# commu.net
KiCad netlist of a schematic drawn in Altium Designer
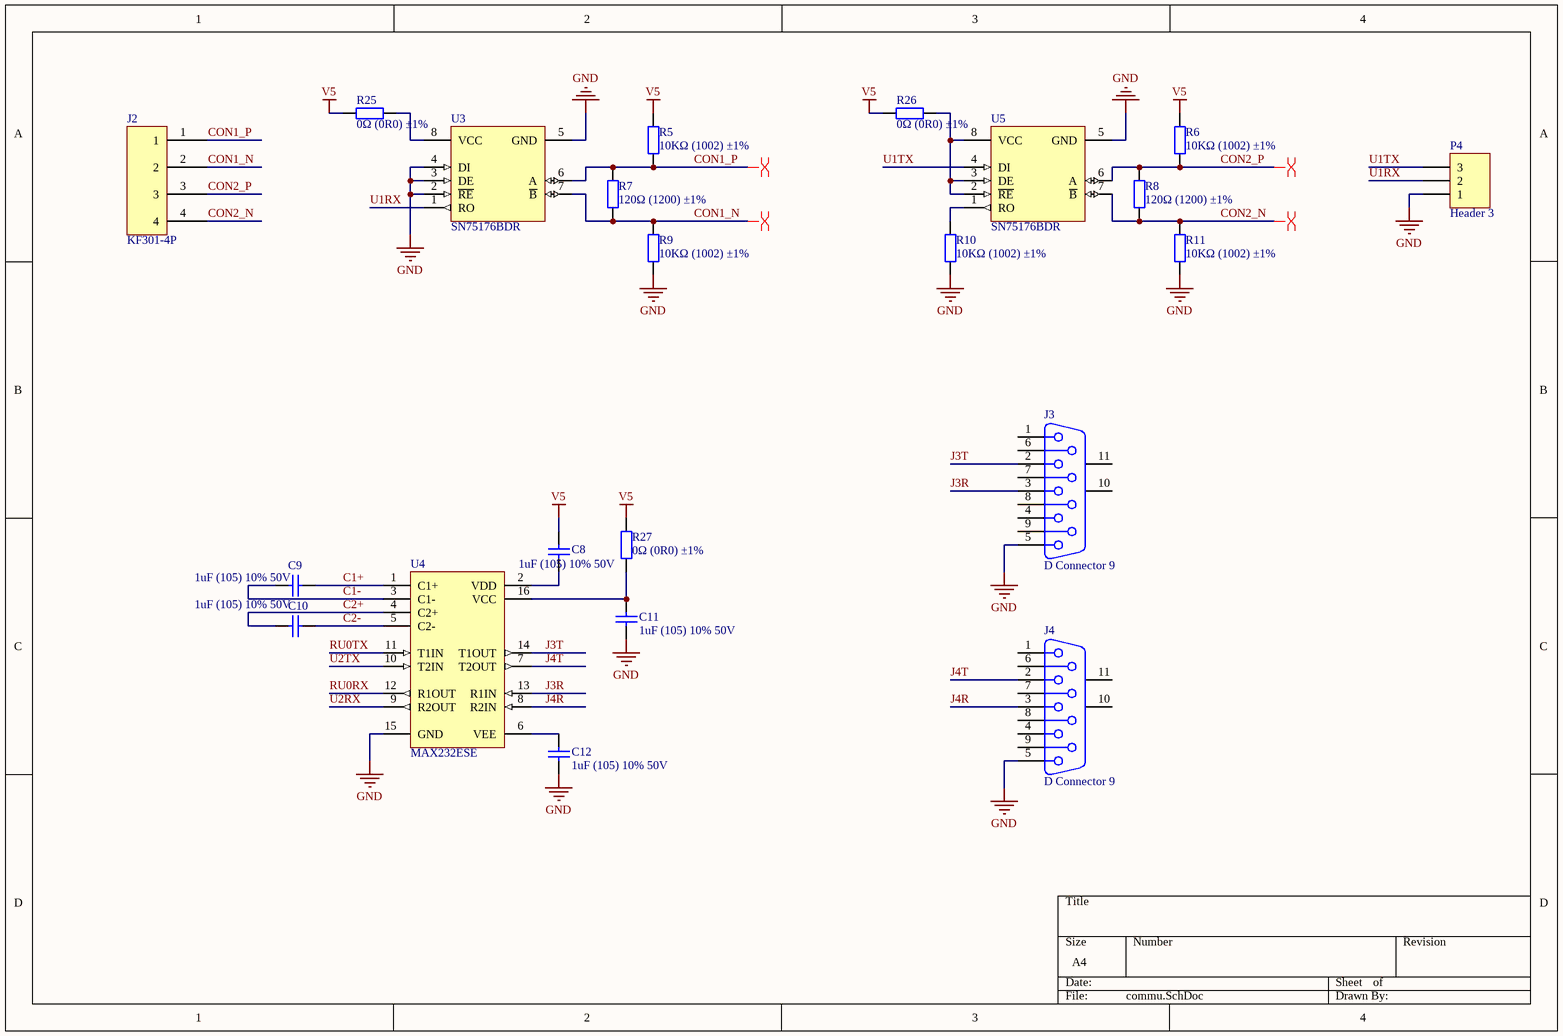
[diagram p0: commu.SchDoc]

(export (version "E")
  (design (tool "Eeschema 10.0.6"))
  (components
    (comp (ref "C8")
      (value "1uF (105) 10% 50V")
      (footprint "0603_C")
      (description "贴片电容")
      (libsource (lib "Miscellaneous Devices LC") (part "0603 1uF (105) 10% 50V"))
    )
    (comp (ref "C9")
      (value "1uF (105) 10% 50V")
      (footprint "0603_C")
      (description "贴片电容")
      (libsource (lib "Miscellaneous Devices LC") (part "0603 1uF (105) 10% 50V"))
    )
    (comp (ref "C10")
      (value "1uF (105) 10% 50V")
      (footprint "0603_C")
      (description "贴片电容")
      (libsource (lib "Miscellaneous Devices LC") (part "0603 1uF (105) 10% 50V"))
    )
    (comp (ref "C11")
      (value "1uF (105) 10% 50V")
      (footprint "0603_C")
      (description "贴片电容")
      (libsource (lib "Miscellaneous Devices LC") (part "0603 1uF (105) 10% 50V"))
    )
    (comp (ref "C12")
      (value "1uF (105) 10% 50V")
      (footprint "0603_C")
      (description "贴片电容")
      (libsource (lib "Miscellaneous Devices LC") (part "0603 1uF (105) 10% 50V"))
    )
    (comp (ref "J2") (value "KF301-4P") (footprint "KF301-4P") (libsource (lib "CHK-I") (part "KF301-4P")))
    (comp (ref "J3")
      (value "D Connector 9")
      (footprint "DSUB1.385-2H9")
      (description "Receptacle Assembly, 9 Position, Right Angle")
      (fields (field (name "PUBLISHER") "Altium Limited"))
      (libsource (lib "Miscellaneous Connectors") (part "D Connector 9"))
    )
    (comp (ref "J4")
      (value "D Connector 9")
      (footprint "DSUB1.385-2H9")
      (description "Receptacle Assembly, 9 Position, Right Angle")
      (fields (field (name "PUBLISHER") "Altium Limited"))
      (libsource (lib "Miscellaneous Connectors") (part "D Connector 9"))
    )
    (comp (ref "P4")
      (value "Header 3")
      (footprint "HDR1X3")
      (description "Header, 3-Pin")
      (fields (field (name "PUBLISHER") "Altium Limited"))
      (libsource (lib "Miscellaneous Connectors") (part "Header 3"))
    )
    (comp (ref "R5")
      (value "10KΩ (1002) ±1%")
      (footprint "0603_R")
      (description "贴片电阻")
      (libsource (lib "Miscellaneous Devices LC") (part "0603 10KΩ (1002) 1%"))
    )
    (comp (ref "R6")
      (value "10KΩ (1002) ±1%")
      (footprint "0603_R")
      (description "贴片电阻")
      (libsource (lib "Miscellaneous Devices LC") (part "0603 10KΩ (1002) 1%"))
    )
    (comp (ref "R7")
      (value "120Ω (1200) ±1%")
      (footprint "0603_R")
      (description "贴片电阻")
      (libsource (lib "Miscellaneous Devices LC") (part "0603 120Ω (1200) 1%"))
    )
    (comp (ref "R8")
      (value "120Ω (1200) ±1%")
      (footprint "0603_R")
      (description "贴片电阻")
      (libsource (lib "Miscellaneous Devices LC") (part "0603 120Ω (1200) 1%"))
    )
    (comp (ref "R9")
      (value "10KΩ (1002) ±1%")
      (footprint "0603_R")
      (description "贴片电阻")
      (libsource (lib "Miscellaneous Devices LC") (part "0603 10KΩ (1002) 1%"))
    )
    (comp (ref "R10")
      (value "10KΩ (1002) ±1%")
      (footprint "0603_R")
      (description "贴片电阻")
      (libsource (lib "Miscellaneous Devices LC") (part "0603 10KΩ (1002) 1%"))
    )
    (comp (ref "R11")
      (value "10KΩ (1002) ±1%")
      (footprint "0603_R")
      (description "贴片电阻")
      (libsource (lib "Miscellaneous Devices LC") (part "0603 10KΩ (1002) 1%"))
    )
    (comp (ref "R25")
      (value "0Ω (0R0) ±1%")
      (footprint "1206_R")
      (description "贴片电阻")
      (libsource (lib "Miscellaneous Devices LC") (part "1206 0Ω (0R0) 1%"))
    )
    (comp (ref "R26")
      (value "0Ω (0R0) ±1%")
      (footprint "1206_R")
      (description "贴片电阻")
      (libsource (lib "Miscellaneous Devices LC") (part "1206 0Ω (0R0) 1%"))
    )
    (comp (ref "R27")
      (value "0Ω (0R0) ±1%")
      (footprint "1206_R")
      (description "贴片电阻")
      (libsource (lib "") (part "1206 0Ω (0R0) 1%_1"))
    )
    (comp (ref "U3")
      (value "SN75176BDR")
      (footprint "SOIC-8_150mil")
      (description "RS-485/RS-422")
      (libsource (lib "Miscellaneous Devices LC") (part "SN75176BDR_[C7063]"))
    )
    (comp (ref "U4")
      (value "MAX232ESE")
      (footprint "SOIC-16_150mil")
      (description "RS232")
      (libsource (lib "Miscellaneous Devices LC") (part "MAX232ESE_[C26860]"))
    )
    (comp (ref "U5")
      (value "SN75176BDR")
      (footprint "SOIC-8_150mil")
      (description "RS-485/RS-422")
      (libsource (lib "Miscellaneous Devices LC") (part "SN75176BDR_[C7063]"))
    )
  )
  (nets
    (net (code "1") (name "/C1+") (class "Default")
      (node (ref "C9") (pin "2") (pinfunction "2_2") (pintype "passive"))
      (node (ref "U4") (pin "1") (pinfunction "C1+_1") (pintype "passive"))
    )
    (net (code "2") (name "/C1-") (class "Default")
      (node (ref "C9") (pin "1") (pinfunction "1_1") (pintype "passive"))
      (node (ref "U4") (pin "3") (pinfunction "C1-_3") (pintype "passive"))
    )
    (net (code "3") (name "/C2+") (class "Default")
      (node (ref "C10") (pin "1") (pinfunction "1_1") (pintype "passive"))
      (node (ref "U4") (pin "4") (pinfunction "C2+_4") (pintype "passive"))
    )
    (net (code "4") (name "/C2-") (class "Default")
      (node (ref "C10") (pin "2") (pinfunction "2_2") (pintype "passive"))
      (node (ref "U4") (pin "5") (pinfunction "C2-_5") (pintype "passive"))
    )
    (net (code "5") (name "/CON1_N") (class "Default")
      (node (ref "J2") (pin "2") (pinfunction "2_2") (pintype "passive"))
      (node (ref "R7") (pin "1") (pinfunction "1_1") (pintype "passive"))
      (node (ref "R9") (pin "2") (pinfunction "2_2") (pintype "passive"))
      (node (ref "U3") (pin "7") (pinfunction "~{B}_7") (pintype "bidirectional"))
    )
    (net (code "6") (name "/CON1_P") (class "Default")
      (node (ref "J2") (pin "1") (pinfunction "1_1") (pintype "passive"))
      (node (ref "R5") (pin "1") (pinfunction "1_1") (pintype "passive"))
      (node (ref "R7") (pin "2") (pinfunction "2_2") (pintype "passive"))
      (node (ref "U3") (pin "6") (pinfunction "A_6") (pintype "bidirectional"))
    )
    (net (code "7") (name "/CON2_N") (class "Default")
      (node (ref "J2") (pin "4") (pinfunction "4_4") (pintype "passive"))
      (node (ref "R11") (pin "2") (pinfunction "2_2") (pintype "passive"))
      (node (ref "R8") (pin "1") (pinfunction "1_1") (pintype "passive"))
      (node (ref "U5") (pin "7") (pinfunction "~{B}_7") (pintype "bidirectional"))
    )
    (net (code "8") (name "/CON2_P") (class "Default")
      (node (ref "J2") (pin "3") (pinfunction "3_3") (pintype "passive"))
      (node (ref "R6") (pin "1") (pinfunction "1_1") (pintype "passive"))
      (node (ref "R8") (pin "2") (pinfunction "2_2") (pintype "passive"))
      (node (ref "U5") (pin "6") (pinfunction "A_6") (pintype "bidirectional"))
    )
    (net (code "9") (name "/J3R") (class "Default")
      (node (ref "J3") (pin "3") (pinfunction "3_3") (pintype "passive"))
      (node (ref "U4") (pin "13") (pinfunction "R1IN_13") (pintype "input"))
    )
    (net (code "10") (name "/J3T") (class "Default")
      (node (ref "J3") (pin "2") (pinfunction "2_2") (pintype "passive"))
      (node (ref "U4") (pin "14") (pinfunction "T1OUT_14") (pintype "output"))
    )
    (net (code "11") (name "/J4R") (class "Default")
      (node (ref "J4") (pin "3") (pinfunction "3_3") (pintype "passive"))
      (node (ref "U4") (pin "8") (pinfunction "R2IN_8") (pintype "input"))
    )
    (net (code "12") (name "/J4T") (class "Default")
      (node (ref "J4") (pin "2") (pinfunction "2_2") (pintype "passive"))
      (node (ref "U4") (pin "7") (pinfunction "T2OUT_7") (pintype "output"))
    )
    (net (code "13") (name "/RU0RX") (class "Default")
      (node (ref "U4") (pin "12") (pinfunction "R1OUT_12") (pintype "output"))
    )
    (net (code "14") (name "/RU0TX") (class "Default")
      (node (ref "U4") (pin "11") (pinfunction "T1IN_11") (pintype "input"))
    )
    (net (code "15") (name "/U1RX") (class "Default")
      (node (ref "P4") (pin "2") (pinfunction "2_2") (pintype "passive"))
      (node (ref "U3") (pin "1") (pinfunction "RO_1") (pintype "output"))
    )
    (net (code "16") (name "/U1TX") (class "Default")
      (node (ref "P4") (pin "3") (pinfunction "3_3") (pintype "passive"))
      (node (ref "U5") (pin "4") (pinfunction "DI_4") (pintype "input"))
    )
    (net (code "17") (name "/U2RX") (class "Default")
      (node (ref "U4") (pin "9") (pinfunction "R2OUT_9") (pintype "output"))
    )
    (net (code "18") (name "/U2TX") (class "Default")
      (node (ref "U4") (pin "10") (pinfunction "T2IN_10") (pintype "input"))
    )
    (net (code "19") (name "GND") (class "Default")
      (node (ref "C11") (pin "1") (pinfunction "1_1") (pintype "passive"))
      (node (ref "C12") (pin "1") (pinfunction "1_1") (pintype "passive"))
      (node (ref "J3") (pin "5") (pinfunction "5_5") (pintype "passive"))
      (node (ref "J4") (pin "5") (pinfunction "5_5") (pintype "passive"))
      (node (ref "P4") (pin "1") (pinfunction "1_1") (pintype "passive"))
      (node (ref "R10") (pin "1") (pinfunction "1_1") (pintype "passive"))
      (node (ref "R11") (pin "1") (pinfunction "1_1") (pintype "passive"))
      (node (ref "R9") (pin "1") (pinfunction "1_1") (pintype "passive"))
      (node (ref "U3") (pin "2") (pinfunction "~{RE}_2") (pintype "input"))
      (node (ref "U3") (pin "3") (pinfunction "DE_3") (pintype "input"))
      (node (ref "U3") (pin "4") (pinfunction "DI_4") (pintype "input"))
      (node (ref "U3") (pin "5") (pinfunction "GND_5") (pintype "power_in"))
      (node (ref "U4") (pin "15") (pinfunction "GND_15") (pintype "power_in"))
      (node (ref "U5") (pin "5") (pinfunction "GND_5") (pintype "power_in"))
    )
    (net (code "20") (name "Net-(U3-VCC)") (class "Default")
      (node (ref "R25") (pin "2") (pinfunction "2_2") (pintype "passive"))
      (node (ref "U3") (pin "8") (pinfunction "VCC_8") (pintype "power_in"))
    )
    (net (code "21") (name "Net-(U4-VCC)") (class "Default")
      (node (ref "C11") (pin "2") (pinfunction "2_2") (pintype "passive"))
      (node (ref "R27") (pin "1") (pinfunction "1_1") (pintype "passive"))
      (node (ref "U4") (pin "16") (pinfunction "VCC_16") (pintype "power_in"))
    )
    (net (code "22") (name "Net-(U4-VDD)") (class "Default")
      (node (ref "C8") (pin "1") (pinfunction "1_1") (pintype "passive"))
      (node (ref "U4") (pin "2") (pinfunction "VDD_2") (pintype "power_in"))
    )
    (net (code "23") (name "Net-(U4-VEE)") (class "Default")
      (node (ref "C12") (pin "2") (pinfunction "2_2") (pintype "passive"))
      (node (ref "U4") (pin "6") (pinfunction "VEE_6") (pintype "power_in"))
    )
    (net (code "24") (name "Net-(U5-DE)") (class "Default")
      (node (ref "R26") (pin "2") (pinfunction "2_2") (pintype "passive"))
      (node (ref "U5") (pin "2") (pinfunction "~{RE}_2") (pintype "input"))
      (node (ref "U5") (pin "3") (pinfunction "DE_3") (pintype "input"))
      (node (ref "U5") (pin "8") (pinfunction "VCC_8") (pintype "power_in"))
    )
    (net (code "25") (name "Net-(U5-RO)") (class "Default")
      (node (ref "R10") (pin "2") (pinfunction "2_2") (pintype "passive"))
      (node (ref "U5") (pin "1") (pinfunction "RO_1") (pintype "output"))
    )
    (net (code "26") (name "V5") (class "Default")
      (node (ref "C8") (pin "2") (pinfunction "2_2") (pintype "passive"))
      (node (ref "R25") (pin "1") (pinfunction "1_1") (pintype "passive"))
      (node (ref "R26") (pin "1") (pinfunction "1_1") (pintype "passive"))
      (node (ref "R27") (pin "2") (pinfunction "2_2") (pintype "passive"))
      (node (ref "R5") (pin "2") (pinfunction "2_2") (pintype "passive"))
      (node (ref "R6") (pin "2") (pinfunction "2_2") (pintype "passive"))
    )
    (net (code "27") (name "unconnected-(J3-MH1-Pad10)") (class "Default")
      (node (ref "J3") (pin "10") (pinfunction "MH1_10") (pintype "passive"))
    )
    (net (code "28") (name "unconnected-(J3-MH2-Pad11)") (class "Default")
      (node (ref "J3") (pin "11") (pinfunction "MH2_11") (pintype "passive"))
    )
    (net (code "29") (name "unconnected-(J3-Pad1)") (class "Default")
      (node (ref "J3") (pin "1") (pinfunction "1_1") (pintype "passive"))
    )
    (net (code "30") (name "unconnected-(J3-Pad4)") (class "Default")
      (node (ref "J3") (pin "4") (pinfunction "4_4") (pintype "passive"))
    )
    (net (code "31") (name "unconnected-(J3-Pad6)") (class "Default")
      (node (ref "J3") (pin "6") (pinfunction "6_6") (pintype "passive"))
    )
    (net (code "32") (name "unconnected-(J3-Pad7)") (class "Default")
      (node (ref "J3") (pin "7") (pinfunction "7_7") (pintype "passive"))
    )
    (net (code "33") (name "unconnected-(J3-Pad8)") (class "Default")
      (node (ref "J3") (pin "8") (pinfunction "8_8") (pintype "passive"))
    )
    (net (code "34") (name "unconnected-(J3-Pad9)") (class "Default")
      (node (ref "J3") (pin "9") (pinfunction "9_9") (pintype "passive"))
    )
    (net (code "35") (name "unconnected-(J4-MH1-Pad10)") (class "Default")
      (node (ref "J4") (pin "10") (pinfunction "MH1_10") (pintype "passive"))
    )
    (net (code "36") (name "unconnected-(J4-MH2-Pad11)") (class "Default")
      (node (ref "J4") (pin "11") (pinfunction "MH2_11") (pintype "passive"))
    )
    (net (code "37") (name "unconnected-(J4-Pad1)") (class "Default")
      (node (ref "J4") (pin "1") (pinfunction "1_1") (pintype "passive"))
    )
    (net (code "38") (name "unconnected-(J4-Pad4)") (class "Default")
      (node (ref "J4") (pin "4") (pinfunction "4_4") (pintype "passive"))
    )
    (net (code "39") (name "unconnected-(J4-Pad6)") (class "Default")
      (node (ref "J4") (pin "6") (pinfunction "6_6") (pintype "passive"))
    )
    (net (code "40") (name "unconnected-(J4-Pad7)") (class "Default")
      (node (ref "J4") (pin "7") (pinfunction "7_7") (pintype "passive"))
    )
    (net (code "41") (name "unconnected-(J4-Pad8)") (class "Default")
      (node (ref "J4") (pin "8") (pinfunction "8_8") (pintype "passive"))
    )
    (net (code "42") (name "unconnected-(J4-Pad9)") (class "Default")
      (node (ref "J4") (pin "9") (pinfunction "9_9") (pintype "passive"))
    )
  )
)
